# ad9851.net
KiCad netlist of a schematic drawn in Altium Designer
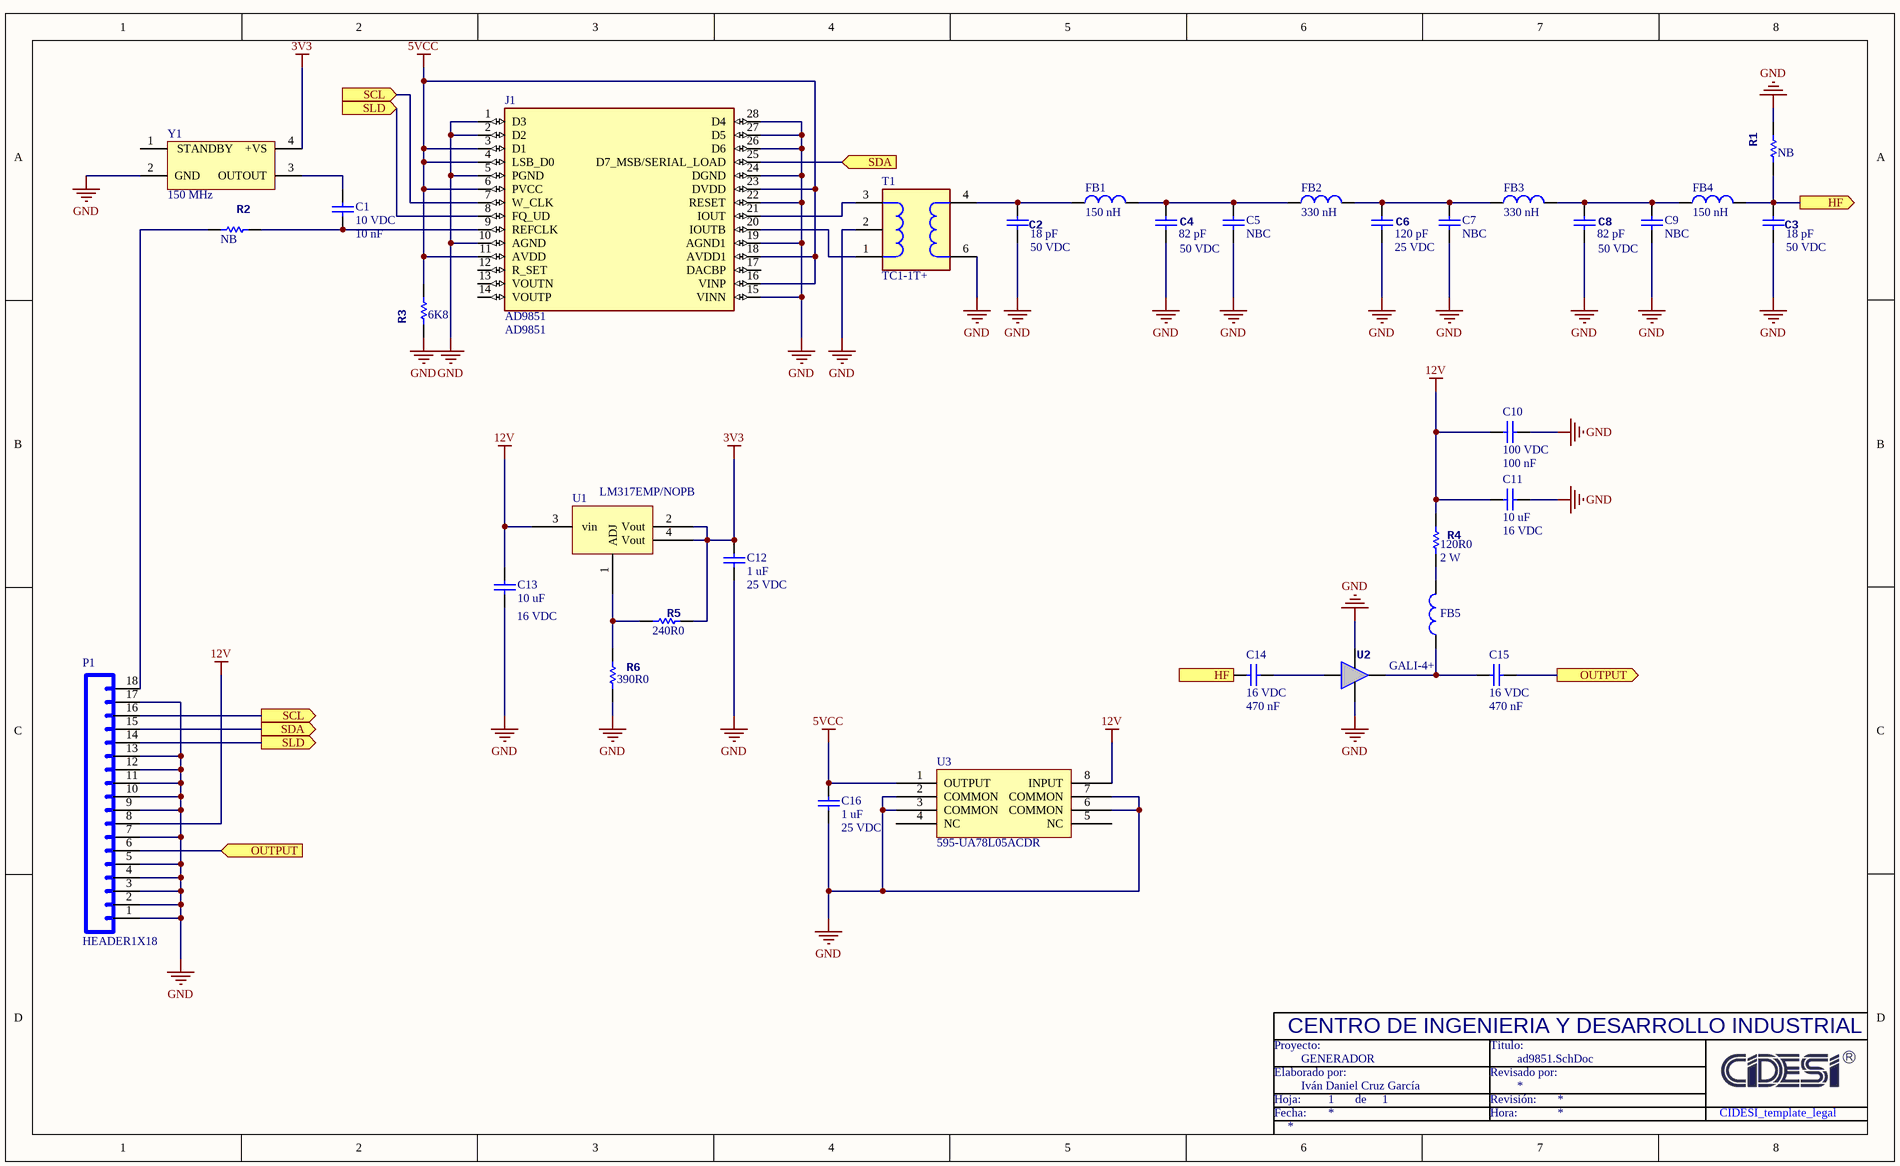
[diagram p0: ad9851.SchDoc]

(export (version "E")
  (design (tool "Eeschema 10.0.6"))
  (components
    (comp (ref "C1")
      (value "10nF, 10V")
      (footprint "C0603")
      (description "Cap_Cer")
      (fields
        (field (name "MANUFACTURER") "Murata Electronics")
        (field (name "MANUFACTURER PART NUMBER") "GRM1857U1A103JA44D")
        (field (name "VOLTAGE RATING DC") "10 VDC")
        (field (name "CAPACITANCE - NF") "10 nF")
      )
      (libsource (lib "AD9851") (part "10nF, 10V"))
    )
    (comp (ref "C2")
      (value "18pF, 50V")
      (footprint "C0603")
      (description "Cap_Cer")
      (fields
        (field (name "MANUFACTURER") "AVX")
        (field (name "MANUFACTURER PART NUMBER") "06035A180J4T2A")
        (field (name "CAPACITANCE") "18 pF")
        (field (name "VOLTAGE RATING DC") "50 VDC")
      )
      (libsource (lib "AD9851") (part "18pF, 50V"))
    )
    (comp (ref "C3")
      (value "18pF, 50V")
      (footprint "C0603")
      (description "Cap_Cer")
      (fields
        (field (name "MANUFACTURER") "AVX")
        (field (name "MANUFACTURER PART NUMBER") "06035A180J4T2A")
        (field (name "CAPACITANCE") "18 pF")
        (field (name "VOLTAGE RATING DC") "50 VDC")
      )
      (libsource (lib "AD9851") (part "18pF, 50V"))
    )
    (comp (ref "C4")
      (value "82pF, 50V")
      (footprint "C0603")
      (description "Cap_Cer")
      (fields
        (field (name "MANUFACTURER") "AVX")
        (field (name "MANUFACTURER PART NUMBER") "06035A820KAT2A")
        (field (name "CAPACITANCE") "82 pF")
        (field (name "VOLTAGE RATING DC") "50 VDC")
      )
      (libsource (lib "AD9851") (part "82pF, 50V"))
    )
    (comp (ref "C5")
      (value "NBC")
      (footprint "C0603")
      (description "Cap_Cer")
      (libsource (lib "AD9851") (part "NBC"))
    )
    (comp (ref "C6")
      (value "120pF, 50V")
      (footprint "C0603")
      (description "Cap_Cer")
      (fields
        (field (name "MANUFACTURER") "AVX")
        (field (name "MANUFACTURER PART NUMBER") "06033A121KAT2A")
        (field (name "CAPACITANCE") "120 pF")
        (field (name "VOLTAGE RATING DC") "25 VDC")
      )
      (libsource (lib "AD9851") (part "120pF, 50V"))
    )
    (comp (ref "C7")
      (value "NBC")
      (footprint "C0603")
      (description "Cap_Cer")
      (libsource (lib "AD9851") (part "NBC"))
    )
    (comp (ref "C8")
      (value "82pF, 50V")
      (footprint "C0603")
      (description "Cap_Cer")
      (fields
        (field (name "MANUFACTURER") "AVX")
        (field (name "MANUFACTURER PART NUMBER") "06035A820KAT2A")
        (field (name "CAPACITANCE") "82 pF")
        (field (name "VOLTAGE RATING DC") "50 VDC")
      )
      (libsource (lib "AD9851") (part "82pF, 50V"))
    )
    (comp (ref "C9")
      (value "NBC")
      (footprint "C0603")
      (description "Cap_Cer")
      (libsource (lib "AD9851") (part "NBC"))
    )
    (comp (ref "C10")
      (value "100nF, 16V")
      (footprint "C0603")
      (description "Cap_Cer")
      (fields
        (field (name "MANUFACTURER") "Murata Electronics")
        (field (name "MANUFACTURER PART NUMBER") "GRM188R72A104KA35J")
        (field (name "VOLTAGE RATING DC") "100 VDC")
        (field (name "CAPACITANCE - NF") "100 nF")
      )
      (libsource (lib "AD9851") (part "100nF, 16V"))
    )
    (comp (ref "C11")
      (value "10uF, 16V")
      (footprint "C0603")
      (description "Cap_Cer")
      (fields
        (field (name "MANUFACTURER") "Murata Electronics")
        (field (name "MANUFACTURER PART NUMBER") "GRM188C81C106MA73D")
        (field (name "CAPACITANCE") "10 uF")
        (field (name "VOLTAGE RATING DC") "16 VDC")
      )
      (libsource (lib "AD9851") (part "10uF, 16V"))
    )
    (comp (ref "C12")
      (value "1uF, 25V")
      (footprint "C0603")
      (description "Cap_Cer")
      (fields
        (field (name "MANUFACTURER") "AVX")
        (field (name "MANUFACTURER PART NUMBER") "06033C105KAT2A")
        (field (name "CAPACITANCE") "1 uF")
        (field (name "VOLTAGE RATING DC") "25 VDC")
      )
      (libsource (lib "AD9851") (part "1uF, 25V"))
    )
    (comp (ref "C13")
      (value "10uF, 16V")
      (footprint "C0603")
      (description "Cap_Cer")
      (fields
        (field (name "MANUFACTURER") "Murata Electronics")
        (field (name "MANUFACTURER PART NUMBER") "GRM188C81C106MA73D")
        (field (name "CAPACITANCE") "10 uF")
        (field (name "VOLTAGE RATING DC") "16 VDC")
      )
      (libsource (lib "AD9851") (part "10uF, 16V"))
    )
    (comp (ref "C14")
      (value "470nF, 16V")
      (footprint "C0603")
      (description "Cap_Cer")
      (fields
        (field (name "MANUFACTURER") "KEMET")
        (field (name "MANUFACTURER PART NUMBER") "C0603X474J4RACTU")
        (field (name "VOLTAGE RATING DC") "16 VDC")
        (field (name "CAPACITANCE - NF") "470 nF")
      )
      (libsource (lib "AD9851") (part "470nF, 16V"))
    )
    (comp (ref "C15")
      (value "470nF, 16V")
      (footprint "C0603")
      (description "Cap_Cer")
      (fields
        (field (name "MANUFACTURER") "KEMET")
        (field (name "MANUFACTURER PART NUMBER") "C0603X474J4RACTU")
        (field (name "VOLTAGE RATING DC") "16 VDC")
        (field (name "CAPACITANCE - NF") "470 nF")
      )
      (libsource (lib "AD9851") (part "470nF, 16V"))
    )
    (comp (ref "C16")
      (value "1uF, 25V")
      (footprint "C0603")
      (description "Cap_Cer")
      (fields
        (field (name "MANUFACTURER") "AVX")
        (field (name "MANUFACTURER PART NUMBER") "06033C105KAT2A")
        (field (name "CAPACITANCE") "1 uF")
        (field (name "VOLTAGE RATING DC") "25 VDC")
      )
      (libsource (lib "AD9851") (part "1uF, 25V"))
    )
    (comp (ref "FB1")
      (value "150nH")
      (footprint "SIMID 0805")
      (description "Inductor")
      (fields
        (field (name "MANUFACTURER") "EPCOS / TDK")
        (field (name "MANUFACTURER PART NUMBER") "B82498F3151G000")
        (field (name "INDUCTANCE") "150 nH")
      )
      (libsource (lib "AD9851") (part "150nH"))
    )
    (comp (ref "FB2")
      (value "330nH")
      (footprint "SIMID 0805")
      (description "Inductor")
      (fields
        (field (name "MANUFACTURER") "EPCOS / TDK")
        (field (name "MANUFACTURER PART NUMBER") "B82498F3331J")
        (field (name "INDUCTANCE") "330 nH")
      )
      (libsource (lib "AD9851") (part "330nH"))
    )
    (comp (ref "FB3")
      (value "330nH")
      (footprint "SIMID 0805")
      (description "Inductor")
      (fields
        (field (name "MANUFACTURER") "EPCOS / TDK")
        (field (name "MANUFACTURER PART NUMBER") "B82498F3331J")
        (field (name "INDUCTANCE") "330 nH")
      )
      (libsource (lib "AD9851") (part "330nH"))
    )
    (comp (ref "FB4")
      (value "150nH")
      (footprint "SIMID 0805")
      (description "Inductor")
      (fields
        (field (name "MANUFACTURER") "EPCOS / TDK")
        (field (name "MANUFACTURER PART NUMBER") "B82498F3151G000")
        (field (name "INDUCTANCE") "150 nH")
      )
      (libsource (lib "AD9851") (part "150nH"))
    )
    (comp (ref "FB5")
      (value "NBI")
      (footprint "SIMID 0805")
      (description "Inductor")
      (libsource (lib "AD9851") (part "NBI"))
    )
    (comp (ref "J1")
      (value "AD9851")
      (footprint "TSSOP28")
      (description "DDS/DAC Synthesizer")
      (fields
        (field (name "MANUFACTURER") "Analog Devices")
        (field (name "MANUFACTURER PART NUMBER") "AD9851BRSZ")
        (field (name "SERIES") "AD9851")
      )
      (libsource (lib "AD9851") (part "AD9851"))
    )
    (comp (ref "P1")
      (value "HEADER1X18")
      (footprint "HEAD9-90")
      (description "HEADER")
      (fields
        (field (name "MANUFACTURER") "Amphenol FCI")
        (field (name "MANUFACTURER PART NUMBER") "68000-236HLF")
      )
      (libsource (lib "AD9851") (part "HEADER1X18"))
    )
    (comp (ref "R1")
      (value "NB")
      (footprint "RESC0603")
      (description "Resistor")
      (fields (field (name "RESISTANCE") "NB"))
      (libsource (lib "AD9851") (part "NB"))
    )
    (comp (ref "R2")
      (value "NB")
      (footprint "RESC0603")
      (description "Resistor")
      (fields (field (name "RESISTANCE") "NB"))
      (libsource (lib "AD9851") (part "NB"))
    )
    (comp (ref "R3")
      (value "6K8, 100mW")
      (footprint "RESC0603")
      (description "Resistor")
      (fields
        (field (name "MANUFACTURER") "Vishay / Dale")
        (field (name "MANUFACTURER PART NUMBER") "CRCW06036K80JNEA")
        (field (name "RESISTANCE") "6K8")
      )
      (libsource (lib "AD9851") (part "6K8, 100mW"))
    )
    (comp (ref "R4")
      (value "120R0, 2W")
      (footprint "RESC2512")
      (description "Resistor")
      (fields
        (field (name "MANUFACTURER") "Yageo")
        (field (name "MANUFACTURER PART NUMBER") "RC2512FK-7W120RL")
        (field (name "RESISTANCE") "120R0")
        (field (name "POWER RATING") "2 W")
      )
      (libsource (lib "AD9851") (part "120R0, 2W"))
    )
    (comp (ref "R5")
      (value "240R0, 100mW")
      (footprint "RESC0603")
      (description "Resistor")
      (fields
        (field (name "MANUFACTURER") "Vishay / Dale")
        (field (name "MANUFACTURER PART NUMBER") "CRCW0603240RFKEAC")
        (field (name "RESISTANCE") "240R0")
      )
      (libsource (lib "AD9851") (part "240R0, 100mW"))
    )
    (comp (ref "R6")
      (value "390R0, 100mW")
      (footprint "RESC0603")
      (description "Resistor")
      (fields
        (field (name "MANUFACTURER") "Vishay / Dale")
        (field (name "MANUFACTURER PART NUMBER") "CRCW0603390RFKEA")
        (field (name "RESISTANCE") "390R0")
      )
      (libsource (lib "AD9851") (part "390R0, 100mW"))
    )
    (comp (ref "T1")
      (value "Transformer")
      (footprint "Mini-Circuits_0_MFG")
      (description "Signal Transformers")
      (fields
        (field (name "MANUFACTURER") "Mini-Circuits")
        (field (name "MANUFACTURER PART NUMBER") "TC1-1T+")
      )
      (libsource (lib "AD9851") (part "Transformer"))
    )
    (comp (ref "U1")
      (value "LM317EMP 3V3")
      (footprint "SOT-223-4")
      (description "Voltage Regulator")
      (fields
        (field (name "MANUFACTURER") "Texas Instruments")
        (field (name "MANUFACTURER PART NUMBER") "LM317EMP/NOPB")
      )
      (libsource (lib "AD9851") (part "LM317EMP 3V3"))
    )
    (comp (ref "U2")
      (value "GALI-4+")
      (footprint "SOT-89-3")
      (description "AMPLIFIER")
      (fields
        (field (name "MANUFACTURER") "Mini-Circuits")
        (field (name "MANUFACTURER PART NUMBER") "GALI-4+")
      )
      (libsource (lib "AD9851") (part "GALI-4+"))
    )
    (comp (ref "U3")
      (value "Voltage Regulator 5V")
      (footprint "SOIC8")
      (description "Voltage Regulator")
      (fields
        (field (name "MANUFACTURER") "Texas Instruments")
        (field (name "MANUFACTURER PART NUMBER") "UA78L05ACDR")
        (field (name "SUPPLIER PART NUMBER 1") "595-UA78L05ACDR")
      )
      (libsource (lib "AD9851") (part "Voltage Regulator 5V"))
    )
    (comp (ref "Y1")
      (value "OSCILATOR")
      (footprint "OScilator")
      (description "Crystal Oscillator")
      (fields
        (field (name "MANUFACTURER") "ABRACON")
        (field (name "MANUFACTURER PART NUMBER") "ASV-150.000MHZ-E-C-T")
        (field (name "FREQUENCY") "150 MHz")
      )
      (libsource (lib "AD9851") (part "OSCILATOR"))
    )
  )
  (nets
    (net (code "1") (name "/HF") (class "Default")
      (node (ref "C14") (pin "1") (pinfunction "1_1") (pintype "passive"))
      (node (ref "C3") (pin "1") (pinfunction "1_1") (pintype "passive"))
      (node (ref "FB4") (pin "2") (pinfunction "2_2") (pintype "passive"))
      (node (ref "R1") (pin "1") (pinfunction "1_1") (pintype "passive"))
    )
    (net (code "2") (name "/OUTPUT") (class "Default")
      (node (ref "C15") (pin "2") (pinfunction "2_2") (pintype "passive"))
      (node (ref "P1") (pin "6") (pinfunction "6_6") (pintype "passive"))
    )
    (net (code "3") (name "/SCL") (class "Default")
      (node (ref "J1") (pin "7") (pinfunction "W_CLK_7") (pintype "bidirectional"))
      (node (ref "P1") (pin "16") (pinfunction "16_16") (pintype "passive"))
    )
    (net (code "4") (name "/SDA") (class "Default")
      (node (ref "J1") (pin "25") (pinfunction "D7_MSB/SERIAL_LOAD_25") (pintype "bidirectional"))
      (node (ref "P1") (pin "15") (pinfunction "15_15") (pintype "passive"))
    )
    (net (code "5") (name "/SLD") (class "Default")
      (node (ref "J1") (pin "8") (pinfunction "FQ_UD_8") (pintype "bidirectional"))
      (node (ref "P1") (pin "14") (pinfunction "14_14") (pintype "passive"))
    )
    (net (code "6") (name "3V3") (class "Default")
      (node (ref "C12") (pin "2") (pinfunction "2_2") (pintype "passive"))
      (node (ref "R5") (pin "2") (pinfunction "2_2") (pintype "passive"))
      (node (ref "U1") (pin "2") (pinfunction "Vout_2") (pintype "passive"))
      (node (ref "U1") (pin "4") (pinfunction "Vout_4") (pintype "passive"))
      (node (ref "Y1") (pin "4") (pinfunction "+VS_4") (pintype "passive"))
    )
    (net (code "7") (name "5VCC") (class "Default")
      (node (ref "C16") (pin "1") (pinfunction "1_1") (pintype "passive"))
      (node (ref "J1") (pin "11") (pinfunction "AVDD_11") (pintype "bidirectional"))
      (node (ref "J1") (pin "16") (pinfunction "VINP_16") (pintype "bidirectional"))
      (node (ref "J1") (pin "18") (pinfunction "AVDD1_18") (pintype "bidirectional"))
      (node (ref "J1") (pin "23") (pinfunction "DVDD_23") (pintype "bidirectional"))
      (node (ref "J1") (pin "3") (pinfunction "D1_3") (pintype "bidirectional"))
      (node (ref "J1") (pin "4") (pinfunction "LSB_D0_4") (pintype "bidirectional"))
      (node (ref "J1") (pin "6") (pinfunction "PVCC_6") (pintype "bidirectional"))
      (node (ref "R3") (pin "2") (pinfunction "2_2") (pintype "passive"))
      (node (ref "U3") (pin "1") (pinfunction "OUTPUT_1") (pintype "passive"))
    )
    (net (code "8") (name "12V") (class "Default")
      (node (ref "C10") (pin "2") (pinfunction "2_2") (pintype "passive"))
      (node (ref "C11") (pin "1") (pinfunction "1_1") (pintype "passive"))
      (node (ref "C13") (pin "1") (pinfunction "1_1") (pintype "passive"))
      (node (ref "P1") (pin "8") (pinfunction "8_8") (pintype "passive"))
      (node (ref "R4") (pin "2") (pinfunction "2_2") (pintype "passive"))
      (node (ref "U1") (pin "3") (pinfunction "vin_3") (pintype "passive"))
      (node (ref "U3") (pin "8") (pinfunction "INPUT_8") (pintype "passive"))
    )
    (net (code "9") (name "GND") (class "Default")
      (node (ref "C10") (pin "1") (pinfunction "1_1") (pintype "passive"))
      (node (ref "C11") (pin "2") (pinfunction "2_2") (pintype "passive"))
      (node (ref "C12") (pin "1") (pinfunction "1_1") (pintype "passive"))
      (node (ref "C13") (pin "2") (pinfunction "2_2") (pintype "passive"))
      (node (ref "C16") (pin "2") (pinfunction "2_2") (pintype "passive"))
      (node (ref "C2") (pin "2") (pinfunction "2_2") (pintype "passive"))
      (node (ref "C3") (pin "2") (pinfunction "2_2") (pintype "passive"))
      (node (ref "C4") (pin "2") (pinfunction "2_2") (pintype "passive"))
      (node (ref "C5") (pin "2") (pinfunction "2_2") (pintype "passive"))
      (node (ref "C6") (pin "2") (pinfunction "2_2") (pintype "passive"))
      (node (ref "C7") (pin "2") (pinfunction "2_2") (pintype "passive"))
      (node (ref "C8") (pin "2") (pinfunction "2_2") (pintype "passive"))
      (node (ref "C9") (pin "2") (pinfunction "2_2") (pintype "passive"))
      (node (ref "J1") (pin "1") (pinfunction "D3_1") (pintype "bidirectional"))
      (node (ref "J1") (pin "10") (pinfunction "AGND_10") (pintype "bidirectional"))
      (node (ref "J1") (pin "15") (pinfunction "VINN_15") (pintype "bidirectional"))
      (node (ref "J1") (pin "19") (pinfunction "AGND1_19") (pintype "bidirectional"))
      (node (ref "J1") (pin "2") (pinfunction "D2_2") (pintype "bidirectional"))
      (node (ref "J1") (pin "22") (pinfunction "RESET_22") (pintype "bidirectional"))
      (node (ref "J1") (pin "24") (pinfunction "DGND_24") (pintype "bidirectional"))
      (node (ref "J1") (pin "26") (pinfunction "D6_26") (pintype "bidirectional"))
      (node (ref "J1") (pin "27") (pinfunction "D5_27") (pintype "bidirectional"))
      (node (ref "J1") (pin "28") (pinfunction "D4_28") (pintype "bidirectional"))
      (node (ref "J1") (pin "5") (pinfunction "PGND_5") (pintype "bidirectional"))
      (node (ref "P1") (pin "1") (pinfunction "1_1") (pintype "passive"))
      (node (ref "P1") (pin "10") (pinfunction "10_10") (pintype "passive"))
      (node (ref "P1") (pin "11") (pinfunction "11_11") (pintype "passive"))
      (node (ref "P1") (pin "12") (pinfunction "12_12") (pintype "passive"))
      (node (ref "P1") (pin "13") (pinfunction "13_13") (pintype "passive"))
      (node (ref "P1") (pin "17") (pinfunction "17_17") (pintype "passive"))
      (node (ref "P1") (pin "2") (pinfunction "2_2") (pintype "passive"))
      (node (ref "P1") (pin "3") (pinfunction "3_3") (pintype "passive"))
      (node (ref "P1") (pin "4") (pinfunction "4_4") (pintype "passive"))
      (node (ref "P1") (pin "5") (pinfunction "5_5") (pintype "passive"))
      (node (ref "P1") (pin "7") (pinfunction "7_7") (pintype "passive"))
      (node (ref "P1") (pin "9") (pinfunction "9_9") (pintype "passive"))
      (node (ref "R1") (pin "2") (pinfunction "2_2") (pintype "passive"))
      (node (ref "R3") (pin "1") (pinfunction "1_1") (pintype "passive"))
      (node (ref "R6") (pin "1") (pinfunction "1_1") (pintype "passive"))
      (node (ref "T1") (pin "2") (pinfunction "2_2") (pintype "passive"))
      (node (ref "T1") (pin "6") (pinfunction "6_6") (pintype "passive"))
      (node (ref "U2") (pin "2") (pinfunction "2_2") (pintype "passive"))
      (node (ref "U2") (pin "4") (pinfunction "4_4") (pintype "passive"))
      (node (ref "U3") (pin "2") (pinfunction "COMMON_2") (pintype "passive"))
      (node (ref "U3") (pin "3") (pinfunction "COMMON_3") (pintype "passive"))
      (node (ref "U3") (pin "6") (pinfunction "COMMON_6") (pintype "passive"))
      (node (ref "U3") (pin "7") (pinfunction "COMMON_7") (pintype "passive"))
      (node (ref "Y1") (pin "2") (pinfunction "GND_2") (pintype "passive"))
    )
    (net (code "10") (name "Net-(C2-Pad1)") (class "Default")
      (node (ref "C2") (pin "1") (pinfunction "1_1") (pintype "passive"))
      (node (ref "FB1") (pin "1") (pinfunction "1_1") (pintype "passive"))
      (node (ref "T1") (pin "4") (pinfunction "4_4") (pintype "passive"))
    )
    (net (code "11") (name "Net-(C4-Pad1)") (class "Default")
      (node (ref "C4") (pin "1") (pinfunction "1_1") (pintype "passive"))
      (node (ref "C5") (pin "1") (pinfunction "1_1") (pintype "passive"))
      (node (ref "FB1") (pin "2") (pinfunction "2_2") (pintype "passive"))
      (node (ref "FB2") (pin "1") (pinfunction "1_1") (pintype "passive"))
    )
    (net (code "12") (name "Net-(C6-Pad1)") (class "Default")
      (node (ref "C6") (pin "1") (pinfunction "1_1") (pintype "passive"))
      (node (ref "C7") (pin "1") (pinfunction "1_1") (pintype "passive"))
      (node (ref "FB2") (pin "2") (pinfunction "2_2") (pintype "passive"))
      (node (ref "FB3") (pin "1") (pinfunction "1_1") (pintype "passive"))
    )
    (net (code "13") (name "Net-(C8-Pad1)") (class "Default")
      (node (ref "C8") (pin "1") (pinfunction "1_1") (pintype "passive"))
      (node (ref "C9") (pin "1") (pinfunction "1_1") (pintype "passive"))
      (node (ref "FB3") (pin "2") (pinfunction "2_2") (pintype "passive"))
      (node (ref "FB4") (pin "1") (pinfunction "1_1") (pintype "passive"))
    )
    (net (code "14") (name "Net-(C14-Pad2)") (class "Default")
      (node (ref "C14") (pin "2") (pinfunction "2_2") (pintype "passive"))
      (node (ref "U2") (pin "1") (pinfunction "1_1") (pintype "passive"))
    )
    (net (code "15") (name "Net-(C15-Pad1)") (class "Default")
      (node (ref "C15") (pin "1") (pinfunction "1_1") (pintype "passive"))
      (node (ref "FB5") (pin "1") (pinfunction "1_1") (pintype "passive"))
      (node (ref "U2") (pin "3") (pinfunction "3_3") (pintype "passive"))
    )
    (net (code "16") (name "Net-(FB5-Pad2)") (class "Default")
      (node (ref "FB5") (pin "2") (pinfunction "2_2") (pintype "passive"))
      (node (ref "R4") (pin "1") (pinfunction "1_1") (pintype "passive"))
    )
    (net (code "17") (name "Net-(J1-IOUT)") (class "Default")
      (node (ref "J1") (pin "21") (pinfunction "IOUT_21") (pintype "bidirectional"))
      (node (ref "T1") (pin "3") (pinfunction "3_3") (pintype "passive"))
    )
    (net (code "18") (name "Net-(J1-IOUTB)") (class "Default")
      (node (ref "J1") (pin "20") (pinfunction "IOUTB_20") (pintype "bidirectional"))
      (node (ref "T1") (pin "1") (pinfunction "1_1") (pintype "passive"))
    )
    (net (code "19") (name "Net-(J1-REFCLK)") (class "Default")
      (node (ref "C1") (pin "2") (pinfunction "2_2") (pintype "passive"))
      (node (ref "J1") (pin "9") (pinfunction "REFCLK_9") (pintype "bidirectional"))
      (node (ref "R2") (pin "2") (pinfunction "2_2") (pintype "passive"))
    )
    (net (code "20") (name "Net-(P1-Pad18)") (class "Default")
      (node (ref "P1") (pin "18") (pinfunction "18_18") (pintype "passive"))
      (node (ref "R2") (pin "1") (pinfunction "1_1") (pintype "passive"))
    )
    (net (code "21") (name "Net-(U1-ADJ)") (class "Default")
      (node (ref "R5") (pin "1") (pinfunction "1_1") (pintype "passive"))
      (node (ref "R6") (pin "2") (pinfunction "2_2") (pintype "passive"))
      (node (ref "U1") (pin "1") (pinfunction "ADJ_1") (pintype "passive"))
    )
    (net (code "22") (name "Net-(Y1-OUTOUT)") (class "Default")
      (node (ref "C1") (pin "1") (pinfunction "1_1") (pintype "passive"))
      (node (ref "Y1") (pin "3") (pinfunction "OUTOUT_3") (pintype "passive"))
    )
    (net (code "23") (name "unconnected-(J1-DACBP-Pad17)") (class "Default")
      (node (ref "J1") (pin "17") (pinfunction "DACBP_17") (pintype "bidirectional"))
    )
    (net (code "24") (name "unconnected-(J1-R_SET-Pad12)") (class "Default")
      (node (ref "J1") (pin "12") (pinfunction "R_SET_12") (pintype "bidirectional"))
    )
    (net (code "25") (name "unconnected-(J1-VOUTN-Pad13)") (class "Default")
      (node (ref "J1") (pin "13") (pinfunction "VOUTN_13") (pintype "bidirectional"))
    )
    (net (code "26") (name "unconnected-(J1-VOUTP-Pad14)") (class "Default")
      (node (ref "J1") (pin "14") (pinfunction "VOUTP_14") (pintype "bidirectional"))
    )
    (net (code "27") (name "unconnected-(U3-NC-Pad4)") (class "Default")
      (node (ref "U3") (pin "4") (pinfunction "NC_4") (pintype "passive"))
    )
    (net (code "28") (name "unconnected-(U3-NC-Pad5)") (class "Default")
      (node (ref "U3") (pin "5") (pinfunction "NC_5") (pintype "passive"))
    )
    (net (code "29") (name "unconnected-(Y1-STANDBY-Pad1)") (class "Default")
      (node (ref "Y1") (pin "1") (pinfunction "STANDBY_1") (pintype "passive"))
    )
  )
)
